# vvcc.net
KiCad netlist of a schematic drawn in EAGLE
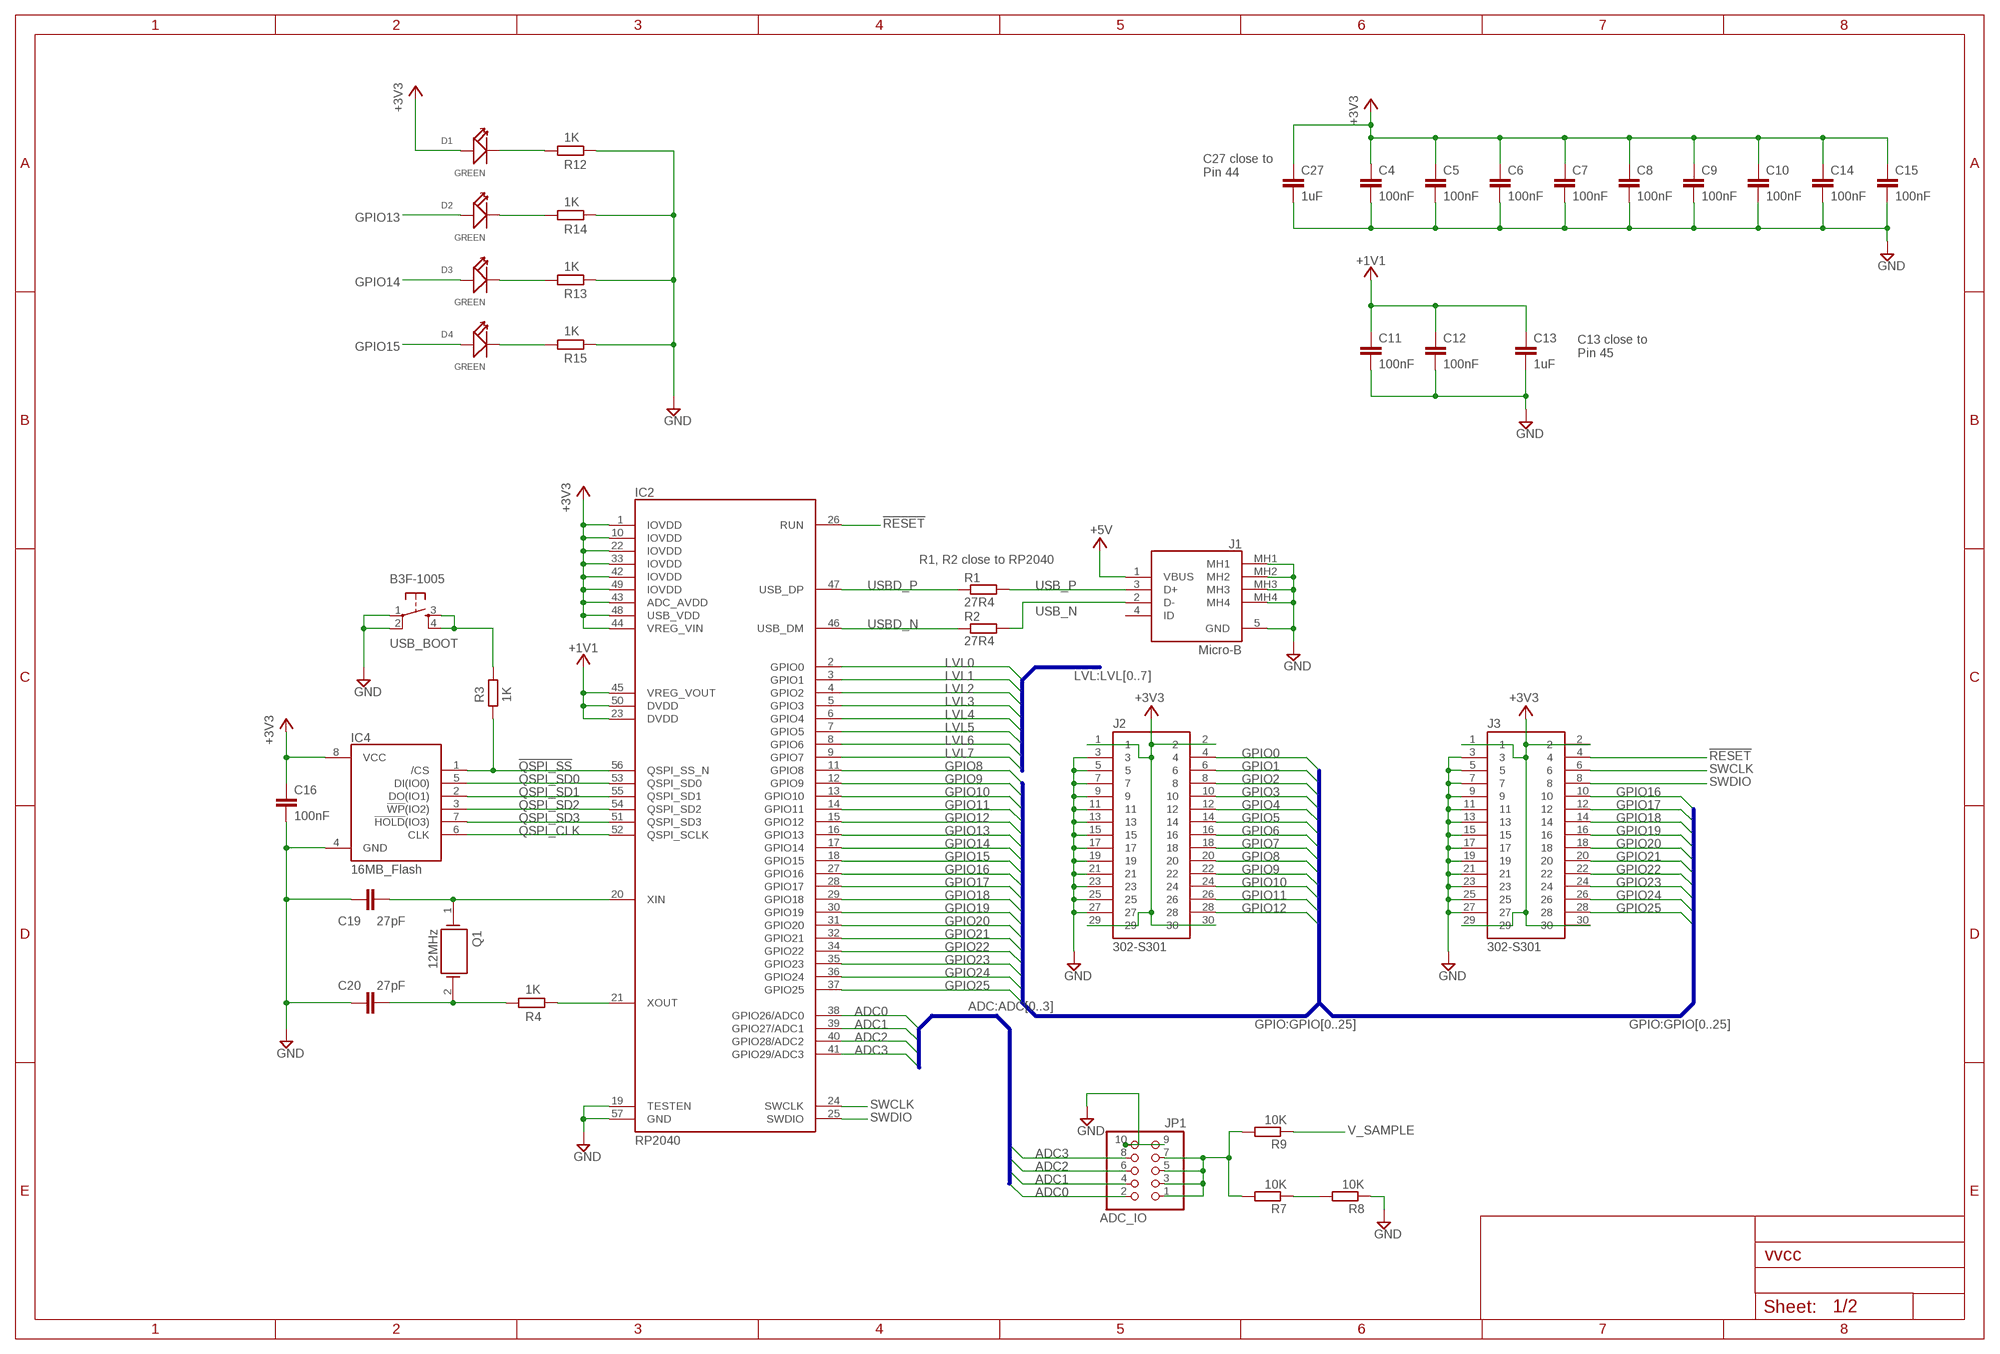
[diagram p0: schematic, sheet 1]
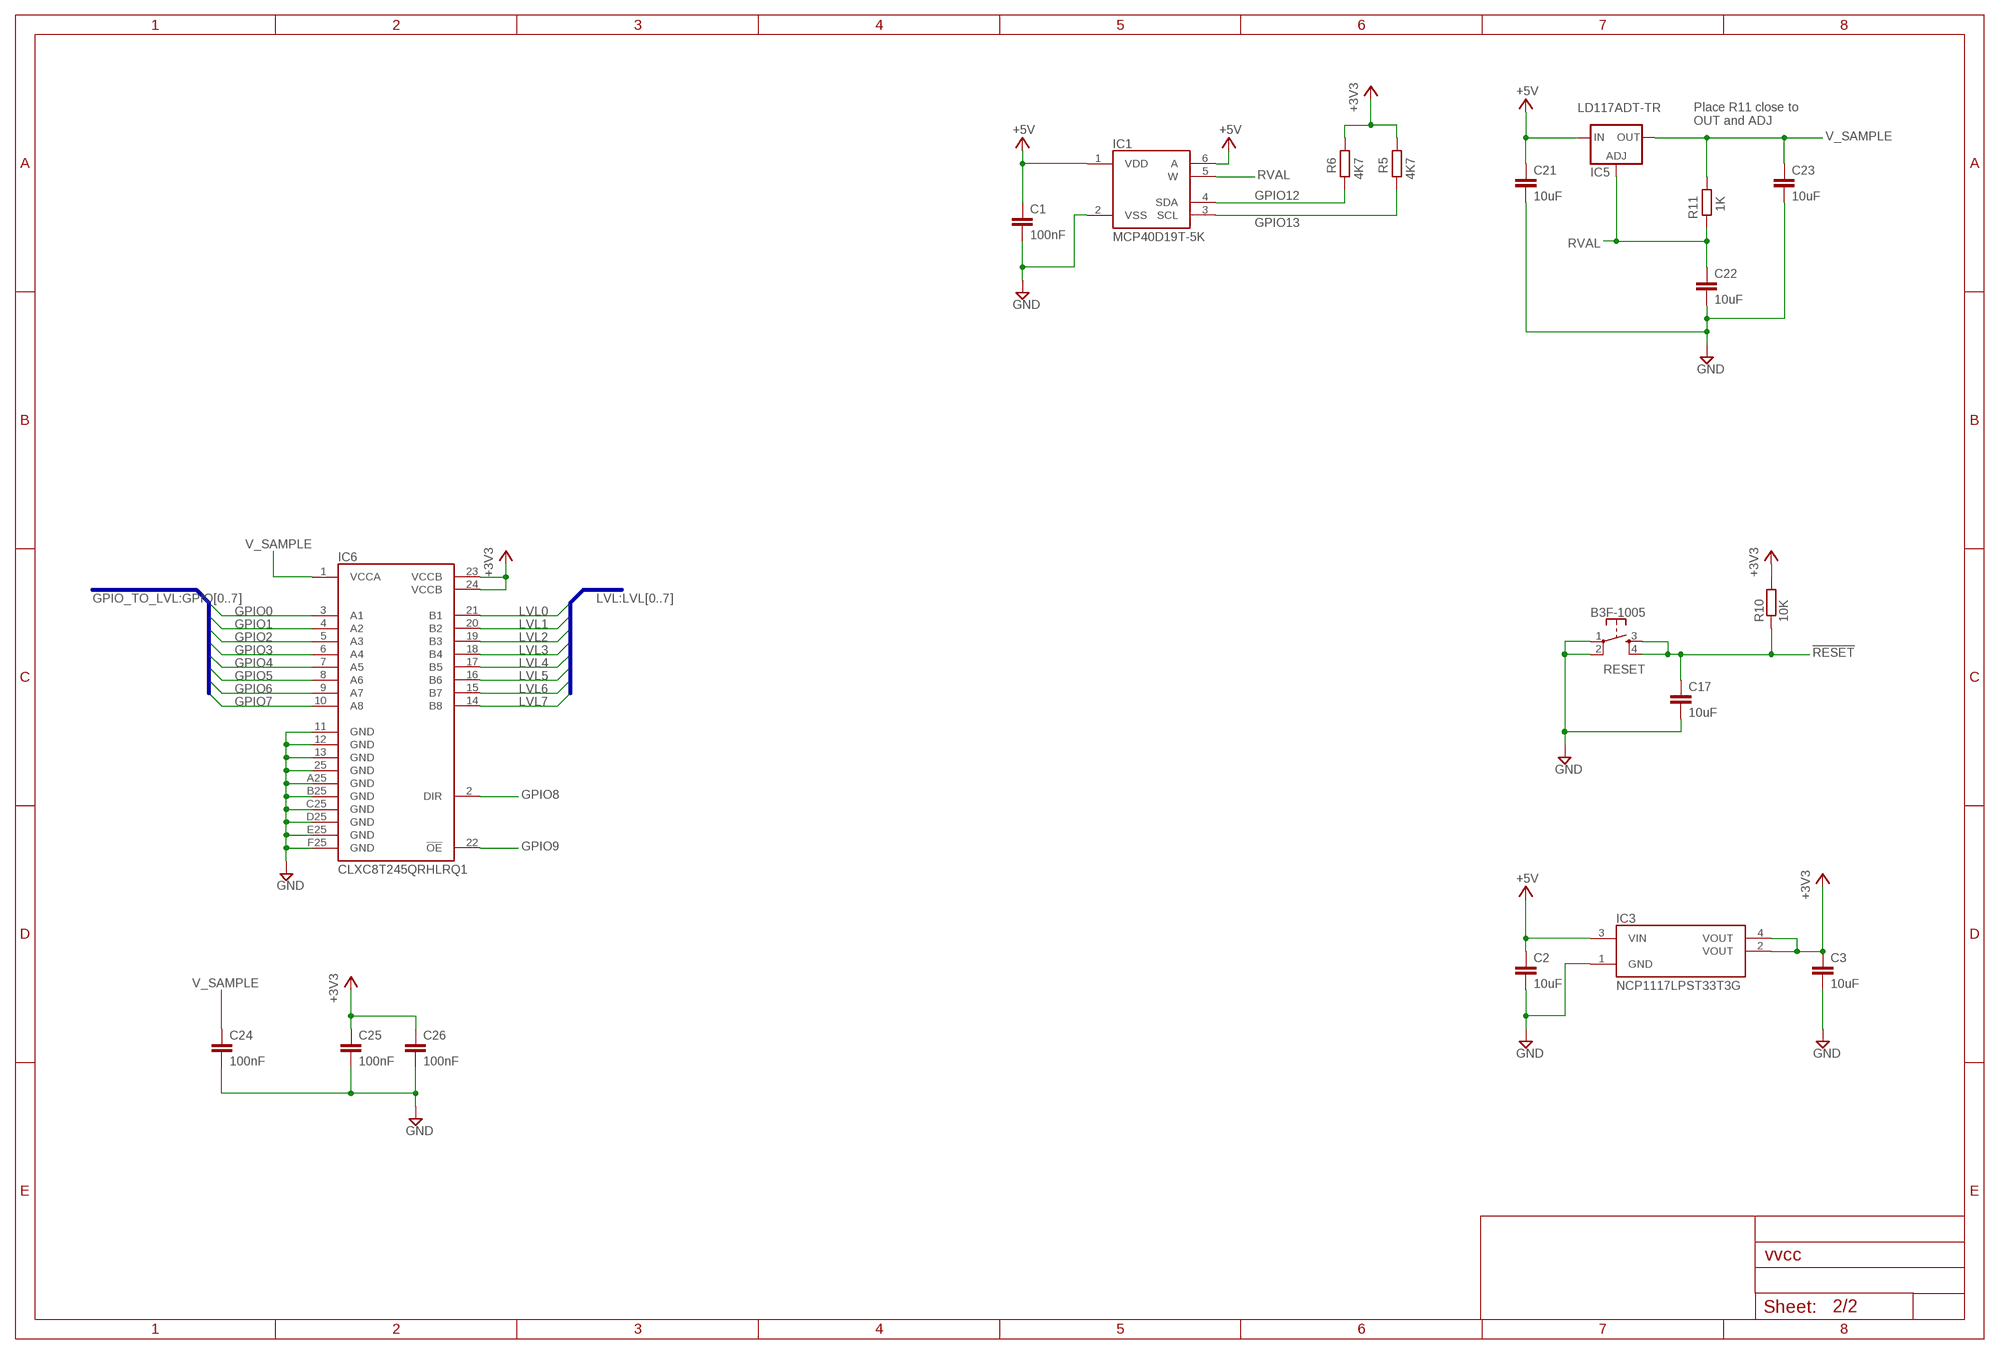
[diagram p1: schematic, sheet 2]

(export (version "E")
  (design (tool "Eeschema 10.0.6"))
  (components
    (comp (ref "C1")
      (value "100nF")
      (footprint "eagle-import:C0201")
      (libsource (lib "eagle-import") (part "C-EUC0201"))
    )
    (comp (ref "C2")
      (value "10uF")
      (footprint "eagle-import:C0402")
      (libsource (lib "eagle-import") (part "C-EUC0402"))
    )
    (comp (ref "C3")
      (value "10uF")
      (footprint "eagle-import:C0402")
      (libsource (lib "eagle-import") (part "C-EUC0402"))
    )
    (comp (ref "C17")
      (value "10uF")
      (footprint "eagle-import:C0402")
      (fields (field (name "USE") "GRM155R60J106ME15D"))
      (libsource (lib "eagle-import") (part "C-EUC0402"))
    )
    (comp (ref "C21")
      (value "10uF")
      (footprint "eagle-import:C0402")
      (libsource (lib "eagle-import") (part "C-EUC0402"))
    )
    (comp (ref "C22")
      (value "10uF")
      (footprint "eagle-import:C0402")
      (libsource (lib "eagle-import") (part "C-EUC0402"))
    )
    (comp (ref "C23")
      (value "10uF")
      (footprint "eagle-import:C0402")
      (libsource (lib "eagle-import") (part "C-EUC0402"))
    )
    (comp (ref "C24")
      (value "100nF")
      (footprint "eagle-import:C0201")
      (libsource (lib "eagle-import") (part "C-EUC0201"))
    )
    (comp (ref "C25")
      (value "100nF")
      (footprint "eagle-import:C0201")
      (libsource (lib "eagle-import") (part "C-EUC0201"))
    )
    (comp (ref "C26")
      (value "100nF")
      (footprint "eagle-import:C0201")
      (libsource (lib "eagle-import") (part "C-EUC0201"))
    )
    (comp (ref "IC1")
      (value "MCP40D19T-5K")
      (footprint "eagle-import:SOP65P210X110-6N")
      (fields
        (field (name "ARROW_PART_NUMBER") "MCP40D18T-104E/LT")
        (field (name "MOUSER_PART_NUMBER") "579-MCP40D18T104E/LT")
      )
      (libsource (lib "eagle-import") (part "MCP40D18T-104E_LT"))
    )
    (comp (ref "IC3")
      (value "NCP1117LPST33T3G")
      (footprint "eagle-import:SOT230P700X180-4N")
      (fields (field (name "MOUSER_PART_NUMBER") "863-NCP1117LPST33T3G"))
      (libsource (lib "eagle-import") (part "NCP1117LPST33T3G"))
    )
    (comp (ref "IC5")
      (value "LD117ADT-TR")
      (footprint "eagle-import:DPACK")
      (libsource (lib "eagle-import") (part "LD117A?DT-TR"))
    )
    (comp (ref "IC6")
      (value "CLXC8T245QRHLRQ1")
      (footprint "eagle-import:CLXC8T245QRHLRQ1")
      (fields (field (name "MOUSER_PART_NUMBER") "595-CLXC8T245QRHLRQ1"))
      (libsource (lib "eagle-import") (part "CLXC8T245QRHLRQ1"))
    )
    (comp (ref "R5")
      (value "4K7")
      (footprint "eagle-import:R0201")
      (libsource (lib "eagle-import") (part "R-EU_R0201"))
    )
    (comp (ref "R6")
      (value "4K7")
      (footprint "eagle-import:R0201")
      (libsource (lib "eagle-import") (part "R-EU_R0201"))
    )
    (comp (ref "R10")
      (value "10K")
      (footprint "eagle-import:R0201")
      (fields (field (name "USE") "CR0201-JW-103GLF"))
      (libsource (lib "eagle-import") (part "R-EU_R0201"))
    )
    (comp (ref "R11")
      (value "1K")
      (footprint "eagle-import:R0201")
      (libsource (lib "eagle-import") (part "R-EU_R0201"))
    )
    (comp (ref "RESET")
      (value "B3F-1005")
      (footprint "eagle-import:TACTILE-PTH")
      (fields (field (name "USE") "B3F-1005"))
      (libsource (lib "eagle-import") (part "TAC_SWITCHPTH"))
    )
    (comp (ref "C4")
      (value "100nF")
      (footprint "eagle-import:C0201")
      (libsource (lib "eagle-import") (part "C-EUC0201"))
    )
    (comp (ref "C5")
      (value "100nF")
      (footprint "eagle-import:C0201")
      (libsource (lib "eagle-import") (part "C-EUC0201"))
    )
    (comp (ref "C6")
      (value "100nF")
      (footprint "eagle-import:C0201")
      (libsource (lib "eagle-import") (part "C-EUC0201"))
    )
    (comp (ref "C7")
      (value "100nF")
      (footprint "eagle-import:C0201")
      (libsource (lib "eagle-import") (part "C-EUC0201"))
    )
    (comp (ref "C8")
      (value "100nF")
      (footprint "eagle-import:C0201")
      (libsource (lib "eagle-import") (part "C-EUC0201"))
    )
    (comp (ref "C9")
      (value "100nF")
      (footprint "eagle-import:C0201")
      (libsource (lib "eagle-import") (part "C-EUC0201"))
    )
    (comp (ref "C10")
      (value "100nF")
      (footprint "eagle-import:C0201")
      (libsource (lib "eagle-import") (part "C-EUC0201"))
    )
    (comp (ref "C11")
      (value "100nF")
      (footprint "eagle-import:C0201")
      (libsource (lib "eagle-import") (part "C-EUC0201"))
    )
    (comp (ref "C12")
      (value "100nF")
      (footprint "eagle-import:C0201")
      (libsource (lib "eagle-import") (part "C-EUC0201"))
    )
    (comp (ref "C13")
      (value "1uF")
      (footprint "eagle-import:C0201")
      (libsource (lib "eagle-import") (part "C-EUC0201"))
    )
    (comp (ref "C14")
      (value "100nF")
      (footprint "eagle-import:C0201")
      (libsource (lib "eagle-import") (part "C-EUC0201"))
    )
    (comp (ref "C15")
      (value "100nF")
      (footprint "eagle-import:C0201")
      (libsource (lib "eagle-import") (part "C-EUC0201"))
    )
    (comp (ref "C16")
      (value "100nF")
      (footprint "eagle-import:C0201")
      (libsource (lib "eagle-import") (part "C-EUC0201"))
    )
    (comp (ref "C19")
      (value "27pF")
      (footprint "eagle-import:C0201")
      (libsource (lib "eagle-import") (part "C-EUC0201"))
    )
    (comp (ref "C20")
      (value "27pF")
      (footprint "eagle-import:C0201")
      (libsource (lib "eagle-import") (part "C-EUC0201"))
    )
    (comp (ref "C27")
      (value "1uF")
      (footprint "eagle-import:C0201")
      (libsource (lib "eagle-import") (part "C-EUC0201"))
    )
    (comp (ref "D1")
      (value "GREEN")
      (footprint "eagle-import:LED-0603")
      (fields (field (name "MPN") "19-217-BHC-ZL1M2RY-3T"))
      (libsource (lib "eagle-import") (part "SMD-LED-CLEAR-BLUE(0603)"))
    )
    (comp (ref "D2")
      (value "GREEN")
      (footprint "eagle-import:LED-0603")
      (fields (field (name "MPN") "19-217-BHC-ZL1M2RY-3T"))
      (libsource (lib "eagle-import") (part "SMD-LED-CLEAR-BLUE(0603)"))
    )
    (comp (ref "D3")
      (value "GREEN")
      (footprint "eagle-import:LED-0603")
      (fields (field (name "MPN") "19-217-BHC-ZL1M2RY-3T"))
      (libsource (lib "eagle-import") (part "SMD-LED-CLEAR-BLUE(0603)"))
    )
    (comp (ref "D4")
      (value "GREEN")
      (footprint "eagle-import:LED-0603")
      (fields (field (name "MPN") "19-217-BHC-ZL1M2RY-3T"))
      (libsource (lib "eagle-import") (part "SMD-LED-CLEAR-BLUE(0603)"))
    )
    (comp (ref "IC2")
      (value "RP2040")
      (footprint "eagle-import:QFN40P700X700X90-57N")
      (libsource (lib "eagle-import") (part "RP2040"))
    )
    (comp (ref "IC4")
      (value "16MB_Flash")
      (footprint "eagle-import:SOIC127P790X216-8N")
      (fields
        (field (name "ARROW_PART_NUMBER") "W25Q128JVSIM TR")
        (field (name "MOUSER_PART_NUMBER") "454-W25Q128JVSIMTR")
      )
      (libsource (lib "eagle-import") (part "W25Q128JVSIM_TR"))
    )
    (comp (ref "J1")
      (value "Micro-B")
      (footprint "eagle-import:MCRBSRASMTCS14TR")
      (fields (field (name "ARROW_PART_NUMBER") "MCR-B-S-RA-SMT-CS14-T/R"))
      (libsource (lib "eagle-import") (part "MCR-B-S-RA-SMT-CS14-T_R"))
    )
    (comp (ref "J2")
      (value "302-S301")
      (footprint "eagle-import:SHDR30W66P254_2X15_4572X910X91")
      (libsource (lib "eagle-import") (part "302-S301"))
    )
    (comp (ref "J3")
      (value "302-S301")
      (footprint "eagle-import:SHDR30W66P254_2X15_4572X910X91")
      (libsource (lib "eagle-import") (part "302-S301"))
    )
    (comp (ref "JP1")
      (value "ADC_IO")
      (footprint "eagle-import:2X05")
      (libsource (lib "eagle-import") (part "PINHD-2X5"))
    )
    (comp (ref "Q1")
      (value "12MHz")
      (footprint "eagle-import:HC_49US-(AT49)_1")
      (fields
        (field (name "ARROW_PART_NUMBER") "ABLS-12.000MHZ-B4-T")
        (field (name "MOUSER_PART_NUMBER") "815-ABLS-12.0M-T")
      )
      (libsource (lib "eagle-import") (part "ABLS-12.000MHZ-B4-T"))
    )
    (comp (ref "R1")
      (value "27R4")
      (footprint "eagle-import:R0201")
      (libsource (lib "eagle-import") (part "R-EU_R0201"))
    )
    (comp (ref "R2")
      (value "27R4")
      (footprint "eagle-import:R0201")
      (libsource (lib "eagle-import") (part "R-EU_R0201"))
    )
    (comp (ref "R3")
      (value "1K")
      (footprint "eagle-import:R0201")
      (libsource (lib "eagle-import") (part "R-EU_R0201"))
    )
    (comp (ref "R4")
      (value "1K")
      (footprint "eagle-import:R0201")
      (libsource (lib "eagle-import") (part "R-EU_R0201"))
    )
    (comp (ref "R7")
      (value "10K")
      (footprint "eagle-import:R0201")
      (fields (field (name "USE") "CR0201-JW-103GLF"))
      (libsource (lib "eagle-import") (part "R-EU_R0201"))
    )
    (comp (ref "R8")
      (value "10K")
      (footprint "eagle-import:R0201")
      (fields (field (name "USE") "CR0201-JW-103GLF"))
      (libsource (lib "eagle-import") (part "R-EU_R0201"))
    )
    (comp (ref "R9")
      (value "10K")
      (footprint "eagle-import:R0201")
      (fields (field (name "USE") "CR0201-JW-103GLF"))
      (libsource (lib "eagle-import") (part "R-EU_R0201"))
    )
    (comp (ref "R12")
      (value "1K")
      (footprint "eagle-import:R0201")
      (libsource (lib "eagle-import") (part "R-EU_R0201"))
    )
    (comp (ref "R13")
      (value "1K")
      (footprint "eagle-import:R0201")
      (libsource (lib "eagle-import") (part "R-EU_R0201"))
    )
    (comp (ref "R14")
      (value "1K")
      (footprint "eagle-import:R0201")
      (libsource (lib "eagle-import") (part "R-EU_R0201"))
    )
    (comp (ref "R15")
      (value "1K")
      (footprint "eagle-import:R0201")
      (libsource (lib "eagle-import") (part "R-EU_R0201"))
    )
    (comp (ref "USB_BOOT")
      (value "B3F-1005")
      (footprint "eagle-import:TACTILE-PTH")
      (fields (field (name "USE") "B3F-1005"))
      (libsource (lib "eagle-import") (part "TAC_SWITCHPTH"))
    )
  )
  (nets
    (net (code "55") (name "+1.8_FT") (class "Default")
      (node (ref "C11") (pin "1") (pinfunction "1_1") (pintype "passive"))
      (node (ref "C12") (pin "1") (pinfunction "1_1") (pintype "passive"))
      (node (ref "C13") (pin "1") (pinfunction "1_1") (pintype "passive"))
      (node (ref "IC2") (pin "23") (pinfunction "DVDD_23") (pintype "bidirectional"))
      (node (ref "IC2") (pin "45") (pinfunction "VREG_VOUT_45") (pintype "bidirectional"))
      (node (ref "IC2") (pin "50") (pinfunction "DVDD_50") (pintype "bidirectional"))
    )
    (net (code "56") (name "+3V3") (class "Default")
      (node (ref "C10") (pin "1") (pinfunction "1_1") (pintype "passive"))
      (node (ref "C14") (pin "1") (pinfunction "1_1") (pintype "passive"))
      (node (ref "C15") (pin "1") (pinfunction "1_1") (pintype "passive"))
      (node (ref "C16") (pin "1") (pinfunction "1_1") (pintype "passive"))
      (node (ref "C25") (pin "1") (pinfunction "1_1") (pintype "passive"))
      (node (ref "C26") (pin "1") (pinfunction "1_1") (pintype "passive"))
      (node (ref "C27") (pin "1") (pinfunction "1_1") (pintype "passive"))
      (node (ref "C3") (pin "1") (pinfunction "1_1") (pintype "passive"))
      (node (ref "C4") (pin "1") (pinfunction "1_1") (pintype "passive"))
      (node (ref "C5") (pin "1") (pinfunction "1_1") (pintype "passive"))
      (node (ref "C6") (pin "1") (pinfunction "1_1") (pintype "passive"))
      (node (ref "C7") (pin "1") (pinfunction "1_1") (pintype "passive"))
      (node (ref "C8") (pin "1") (pinfunction "1_1") (pintype "passive"))
      (node (ref "C9") (pin "1") (pinfunction "1_1") (pintype "passive"))
      (node (ref "D1") (pin "+") (pinfunction "+_+") (pintype "passive"))
      (node (ref "IC2") (pin "1") (pinfunction "IOVDD_1") (pintype "bidirectional"))
      (node (ref "IC2") (pin "10") (pinfunction "IOVDD_10") (pintype "bidirectional"))
      (node (ref "IC2") (pin "22") (pinfunction "IOVDD_22") (pintype "bidirectional"))
      (node (ref "IC2") (pin "33") (pinfunction "IOVDD_33") (pintype "bidirectional"))
      (node (ref "IC2") (pin "42") (pinfunction "IOVDD_42") (pintype "bidirectional"))
      (node (ref "IC2") (pin "43") (pinfunction "ADC_AVDD_43") (pintype "bidirectional"))
      (node (ref "IC2") (pin "44") (pinfunction "VREG_VIN_44") (pintype "bidirectional"))
      (node (ref "IC2") (pin "48") (pinfunction "USB_VDD_48") (pintype "bidirectional"))
      (node (ref "IC2") (pin "49") (pinfunction "IOVDD_49") (pintype "bidirectional"))
      (node (ref "IC3") (pin "2") (pinfunction "VOUT_2") (pintype "bidirectional"))
      (node (ref "IC3") (pin "4") (pinfunction "VOUT_4") (pintype "bidirectional"))
      (node (ref "IC4") (pin "8") (pinfunction "VCC_8") (pintype "bidirectional"))
      (node (ref "IC6") (pin "23") (pinfunction "VCCB_23") (pintype "bidirectional"))
      (node (ref "IC6") (pin "24") (pinfunction "VCCB_24") (pintype "bidirectional"))
      (node (ref "J2") (pin "1") (pinfunction "1_1") (pintype "bidirectional"))
      (node (ref "J2") (pin "2") (pinfunction "2_2") (pintype "bidirectional"))
      (node (ref "J2") (pin "29") (pinfunction "29_29") (pintype "bidirectional"))
      (node (ref "J2") (pin "30") (pinfunction "30_30") (pintype "bidirectional"))
      (node (ref "J3") (pin "1") (pinfunction "1_1") (pintype "bidirectional"))
      (node (ref "J3") (pin "2") (pinfunction "2_2") (pintype "bidirectional"))
      (node (ref "J3") (pin "29") (pinfunction "29_29") (pintype "bidirectional"))
      (node (ref "J3") (pin "30") (pinfunction "30_30") (pintype "bidirectional"))
      (node (ref "R10") (pin "2") (pinfunction "2_2") (pintype "passive"))
      (node (ref "R5") (pin "1") (pinfunction "1_1") (pintype "passive"))
      (node (ref "R6") (pin "1") (pinfunction "1_1") (pintype "passive"))
    )
    (net (code "57") (name "+5V") (class "Default")
      (node (ref "C1") (pin "1") (pinfunction "1_1") (pintype "passive"))
      (node (ref "C2") (pin "1") (pinfunction "1_1") (pintype "passive"))
      (node (ref "C21") (pin "1") (pinfunction "1_1") (pintype "passive"))
      (node (ref "IC1") (pin "1") (pinfunction "VDD_1") (pintype "bidirectional"))
      (node (ref "IC1") (pin "6") (pinfunction "A_6") (pintype "bidirectional"))
      (node (ref "IC3") (pin "3") (pinfunction "VIN_3") (pintype "bidirectional"))
      (node (ref "IC5") (pin "3") (pinfunction "IN_3") (pintype "input"))
      (node (ref "J1") (pin "1") (pinfunction "VBUS_1") (pintype "bidirectional"))
    )
    (net (code "63") (name "ADC0") (class "Default")
      (node (ref "IC2") (pin "38") (pinfunction "GPIO26/ADC0_38") (pintype "bidirectional"))
      (node (ref "JP1") (pin "2") (pinfunction "2_2") (pintype "passive"))
    )
    (net (code "64") (name "ADC1") (class "Default")
      (node (ref "IC2") (pin "39") (pinfunction "GPIO27/ADC1_39") (pintype "bidirectional"))
      (node (ref "JP1") (pin "4") (pinfunction "4_4") (pintype "passive"))
    )
    (net (code "65") (name "ADC2") (class "Default")
      (node (ref "IC2") (pin "40") (pinfunction "GPIO28/ADC2_40") (pintype "bidirectional"))
      (node (ref "JP1") (pin "6") (pinfunction "6_6") (pintype "passive"))
    )
    (net (code "66") (name "ADC3") (class "Default")
      (node (ref "IC2") (pin "41") (pinfunction "GPIO29/ADC3_41") (pintype "bidirectional"))
      (node (ref "JP1") (pin "8") (pinfunction "8_8") (pintype "passive"))
    )
    (net (code "67") (name "GND") (class "Default")
      (node (ref "C1") (pin "2") (pinfunction "2_2") (pintype "passive"))
      (node (ref "C10") (pin "2") (pinfunction "2_2") (pintype "passive"))
      (node (ref "C11") (pin "2") (pinfunction "2_2") (pintype "passive"))
      (node (ref "C12") (pin "2") (pinfunction "2_2") (pintype "passive"))
      (node (ref "C13") (pin "2") (pinfunction "2_2") (pintype "passive"))
      (node (ref "C14") (pin "2") (pinfunction "2_2") (pintype "passive"))
      (node (ref "C15") (pin "2") (pinfunction "2_2") (pintype "passive"))
      (node (ref "C16") (pin "2") (pinfunction "2_2") (pintype "passive"))
      (node (ref "C17") (pin "2") (pinfunction "2_2") (pintype "passive"))
      (node (ref "C19") (pin "2") (pinfunction "2_2") (pintype "passive"))
      (node (ref "C2") (pin "2") (pinfunction "2_2") (pintype "passive"))
      (node (ref "C20") (pin "1") (pinfunction "1_1") (pintype "passive"))
      (node (ref "C21") (pin "2") (pinfunction "2_2") (pintype "passive"))
      (node (ref "C22") (pin "2") (pinfunction "2_2") (pintype "passive"))
      (node (ref "C23") (pin "2") (pinfunction "2_2") (pintype "passive"))
      (node (ref "C24") (pin "2") (pinfunction "2_2") (pintype "passive"))
      (node (ref "C25") (pin "2") (pinfunction "2_2") (pintype "passive"))
      (node (ref "C26") (pin "2") (pinfunction "2_2") (pintype "passive"))
      (node (ref "C27") (pin "2") (pinfunction "2_2") (pintype "passive"))
      (node (ref "C3") (pin "2") (pinfunction "2_2") (pintype "passive"))
      (node (ref "C4") (pin "2") (pinfunction "2_2") (pintype "passive"))
      (node (ref "C5") (pin "2") (pinfunction "2_2") (pintype "passive"))
      (node (ref "C6") (pin "2") (pinfunction "2_2") (pintype "passive"))
      (node (ref "C7") (pin "2") (pinfunction "2_2") (pintype "passive"))
      (node (ref "C8") (pin "2") (pinfunction "2_2") (pintype "passive"))
      (node (ref "C9") (pin "2") (pinfunction "2_2") (pintype "passive"))
      (node (ref "IC1") (pin "2") (pinfunction "VSS_2") (pintype "bidirectional"))
      (node (ref "IC2") (pin "19") (pinfunction "TESTEN_19") (pintype "bidirectional"))
      (node (ref "IC2") (pin "57") (pinfunction "GND_57") (pintype "bidirectional"))
      (node (ref "IC3") (pin "1") (pinfunction "GND_1") (pintype "bidirectional"))
      (node (ref "IC4") (pin "4") (pinfunction "GND_4") (pintype "bidirectional"))
      (node (ref "IC6") (pin "11") (pinfunction "GND_11") (pintype "bidirectional"))
      (node (ref "IC6") (pin "12") (pinfunction "GND_12") (pintype "bidirectional"))
      (node (ref "IC6") (pin "13") (pinfunction "GND_13") (pintype "bidirectional"))
      (node (ref "IC6") (pin "25") (pinfunction "GND_25") (pintype "bidirectional"))
      (node (ref "IC6") (pin "A25") (pinfunction "GND_A25") (pintype "bidirectional"))
      (node (ref "IC6") (pin "B25") (pinfunction "GND_B25") (pintype "bidirectional"))
      (node (ref "IC6") (pin "C25") (pinfunction "GND_C25") (pintype "bidirectional"))
      (node (ref "IC6") (pin "D25") (pinfunction "GND_D25") (pintype "bidirectional"))
      (node (ref "IC6") (pin "E25") (pinfunction "GND_E25") (pintype "bidirectional"))
      (node (ref "IC6") (pin "F25") (pinfunction "GND_F25") (pintype "bidirectional"))
      (node (ref "J1") (pin "5") (pinfunction "GND_5") (pintype "bidirectional"))
      (node (ref "J1") (pin "MH1") (pinfunction "MH1_MH1") (pintype "bidirectional"))
      (node (ref "J1") (pin "MH2") (pinfunction "MH2_MH2") (pintype "bidirectional"))
      (node (ref "J1") (pin "MH3") (pinfunction "MH3_MH3") (pintype "bidirectional"))
      (node (ref "J1") (pin "MH4") (pinfunction "MH4_MH4") (pintype "bidirectional"))
      (node (ref "J2") (pin "11") (pinfunction "11_11") (pintype "bidirectional"))
      (node (ref "J2") (pin "13") (pinfunction "13_13") (pintype "bidirectional"))
      (node (ref "J2") (pin "15") (pinfunction "15_15") (pintype "bidirectional"))
      (node (ref "J2") (pin "17") (pinfunction "17_17") (pintype "bidirectional"))
      (node (ref "J2") (pin "19") (pinfunction "19_19") (pintype "bidirectional"))
      (node (ref "J2") (pin "21") (pinfunction "21_21") (pintype "bidirectional"))
      (node (ref "J2") (pin "23") (pinfunction "23_23") (pintype "bidirectional"))
      (node (ref "J2") (pin "25") (pinfunction "25_25") (pintype "bidirectional"))
      (node (ref "J2") (pin "27") (pinfunction "27_27") (pintype "bidirectional"))
      (node (ref "J2") (pin "3") (pinfunction "3_3") (pintype "bidirectional"))
      (node (ref "J2") (pin "5") (pinfunction "5_5") (pintype "bidirectional"))
      (node (ref "J2") (pin "7") (pinfunction "7_7") (pintype "bidirectional"))
      (node (ref "J2") (pin "9") (pinfunction "9_9") (pintype "bidirectional"))
      (node (ref "J3") (pin "11") (pinfunction "11_11") (pintype "bidirectional"))
      (node (ref "J3") (pin "13") (pinfunction "13_13") (pintype "bidirectional"))
      (node (ref "J3") (pin "15") (pinfunction "15_15") (pintype "bidirectional"))
      (node (ref "J3") (pin "17") (pinfunction "17_17") (pintype "bidirectional"))
      (node (ref "J3") (pin "19") (pinfunction "19_19") (pintype "bidirectional"))
      (node (ref "J3") (pin "21") (pinfunction "21_21") (pintype "bidirectional"))
      (node (ref "J3") (pin "23") (pinfunction "23_23") (pintype "bidirectional"))
      (node (ref "J3") (pin "25") (pinfunction "25_25") (pintype "bidirectional"))
      (node (ref "J3") (pin "27") (pinfunction "27_27") (pintype "bidirectional"))
      (node (ref "J3") (pin "3") (pinfunction "3_3") (pintype "bidirectional"))
      (node (ref "J3") (pin "5") (pinfunction "5_5") (pintype "bidirectional"))
      (node (ref "J3") (pin "7") (pinfunction "7_7") (pintype "bidirectional"))
      (node (ref "J3") (pin "9") (pinfunction "9_9") (pintype "bidirectional"))
      (node (ref "JP1") (pin "10") (pinfunction "10_10") (pintype "passive"))
      (node (ref "JP1") (pin "9") (pinfunction "9_9") (pintype "passive"))
      (node (ref "R12") (pin "2") (pinfunction "2_2") (pintype "passive"))
      (node (ref "R13") (pin "2") (pinfunction "2_2") (pintype "passive"))
      (node (ref "R14") (pin "2") (pinfunction "2_2") (pintype "passive"))
      (node (ref "R15") (pin "2") (pinfunction "2_2") (pintype "passive"))
      (node (ref "R8") (pin "1") (pinfunction "1_1") (pintype "passive"))
      (node (ref "RESET") (pin "1") (pinfunction "1_1") (pintype "passive"))
      (node (ref "RESET") (pin "2") (pinfunction "2_2") (pintype "passive"))
      (node (ref "USB_BOOT") (pin "1") (pinfunction "1_1") (pintype "passive"))
      (node (ref "USB_BOOT") (pin "2") (pinfunction "2_2") (pintype "passive"))
    )
    (net (code "68") (name "GPIO0") (class "Default")
      (node (ref "IC6") (pin "3") (pinfunction "A1_3") (pintype "bidirectional"))
      (node (ref "J2") (pin "4") (pinfunction "4_4") (pintype "bidirectional"))
    )
    (net (code "69") (name "GPIO1") (class "Default")
      (node (ref "IC6") (pin "4") (pinfunction "A2_4") (pintype "bidirectional"))
      (node (ref "J2") (pin "6") (pinfunction "6_6") (pintype "bidirectional"))
    )
    (net (code "70") (name "GPIO2") (class "Default")
      (node (ref "IC6") (pin "5") (pinfunction "A3_5") (pintype "bidirectional"))
      (node (ref "J2") (pin "8") (pinfunction "8_8") (pintype "bidirectional"))
    )
    (net (code "71") (name "GPIO3") (class "Default")
      (node (ref "IC6") (pin "6") (pinfunction "A4_6") (pintype "bidirectional"))
      (node (ref "J2") (pin "10") (pinfunction "10_10") (pintype "bidirectional"))
    )
    (net (code "72") (name "GPIO4") (class "Default")
      (node (ref "IC6") (pin "7") (pinfunction "A5_7") (pintype "bidirectional"))
      (node (ref "J2") (pin "12") (pinfunction "12_12") (pintype "bidirectional"))
    )
    (net (code "73") (name "GPIO5") (class "Default")
      (node (ref "IC6") (pin "8") (pinfunction "A6_8") (pintype "bidirectional"))
      (node (ref "J2") (pin "14") (pinfunction "14_14") (pintype "bidirectional"))
    )
    (net (code "74") (name "GPIO6") (class "Default")
      (node (ref "IC6") (pin "9") (pinfunction "A7_9") (pintype "bidirectional"))
      (node (ref "J2") (pin "16") (pinfunction "16_16") (pintype "bidirectional"))
    )
    (net (code "75") (name "GPIO7") (class "Default")
      (node (ref "IC6") (pin "10") (pinfunction "A8_10") (pintype "bidirectional"))
      (node (ref "J2") (pin "18") (pinfunction "18_18") (pintype "bidirectional"))
    )
    (net (code "76") (name "GPIO8") (class "Default")
      (node (ref "IC2") (pin "11") (pinfunction "GPIO8_11") (pintype "bidirectional"))
      (node (ref "IC6") (pin "2") (pinfunction "DIR_2") (pintype "bidirectional"))
      (node (ref "J2") (pin "20") (pinfunction "20_20") (pintype "bidirectional"))
    )
    (net (code "77") (name "GPIO9") (class "Default")
      (node (ref "IC2") (pin "12") (pinfunction "GPIO9_12") (pintype "bidirectional"))
      (node (ref "IC6") (pin "22") (pinfunction "~{OE}_22") (pintype "bidirectional"))
      (node (ref "J2") (pin "22") (pinfunction "22_22") (pintype "bidirectional"))
    )
    (net (code "78") (name "GPIO10") (class "Default")
      (node (ref "IC2") (pin "13") (pinfunction "GPIO10_13") (pintype "bidirectional"))
      (node (ref "J2") (pin "24") (pinfunction "24_24") (pintype "bidirectional"))
    )
    (net (code "79") (name "GPIO11") (class "Default")
      (node (ref "IC2") (pin "14") (pinfunction "GPIO11_14") (pintype "bidirectional"))
      (node (ref "J2") (pin "26") (pinfunction "26_26") (pintype "bidirectional"))
    )
    (net (code "80") (name "GPIO12") (class "Default")
      (node (ref "IC1") (pin "4") (pinfunction "SDA_4") (pintype "bidirectional"))
      (node (ref "IC2") (pin "15") (pinfunction "GPIO12_15") (pintype "bidirectional"))
      (node (ref "J2") (pin "28") (pinfunction "28_28") (pintype "bidirectional"))
      (node (ref "R6") (pin "2") (pinfunction "2_2") (pintype "passive"))
    )
    (net (code "81") (name "GPIO13") (class "Default")
      (node (ref "D2") (pin "+") (pinfunction "+_+") (pintype "passive"))
      (node (ref "IC1") (pin "3") (pinfunction "SCL_3") (pintype "bidirectional"))
      (node (ref "IC2") (pin "16") (pinfunction "GPIO13_16") (pintype "bidirectional"))
      (node (ref "R5") (pin "2") (pinfunction "2_2") (pintype "passive"))
    )
    (net (code "82") (name "GPIO14") (class "Default")
      (node (ref "D3") (pin "+") (pinfunction "+_+") (pintype "passive"))
      (node (ref "IC2") (pin "17") (pinfunction "GPIO14_17") (pintype "bidirectional"))
    )
    (net (code "83") (name "GPIO15") (class "Default")
      (node (ref "D4") (pin "+") (pinfunction "+_+") (pintype "passive"))
      (node (ref "IC2") (pin "18") (pinfunction "GPIO15_18") (pintype "bidirectional"))
    )
    (net (code "84") (name "GPIO16") (class "Default")
      (node (ref "IC2") (pin "27") (pinfunction "GPIO16_27") (pintype "bidirectional"))
      (node (ref "J3") (pin "10") (pinfunction "10_10") (pintype "bidirectional"))
    )
    (net (code "85") (name "GPIO17") (class "Default")
      (node (ref "IC2") (pin "28") (pinfunction "GPIO17_28") (pintype "bidirectional"))
      (node (ref "J3") (pin "12") (pinfunction "12_12") (pintype "bidirectional"))
    )
    (net (code "86") (name "GPIO18") (class "Default")
      (node (ref "IC2") (pin "29") (pinfunction "GPIO18_29") (pintype "bidirectional"))
      (node (ref "J3") (pin "14") (pinfunction "14_14") (pintype "bidirectional"))
    )
    (net (code "87") (name "GPIO19") (class "Default")
      (node (ref "IC2") (pin "30") (pinfunction "GPIO19_30") (pintype "bidirectional"))
      (node (ref "J3") (pin "16") (pinfunction "16_16") (pintype "bidirectional"))
    )
    (net (code "88") (name "GPIO20") (class "Default")
      (node (ref "IC2") (pin "31") (pinfunction "GPIO20_31") (pintype "bidirectional"))
      (node (ref "J3") (pin "18") (pinfunction "18_18") (pintype "bidirectional"))
    )
    (net (code "89") (name "GPIO21") (class "Default")
      (node (ref "IC2") (pin "32") (pinfunction "GPIO21_32") (pintype "bidirectional"))
      (node (ref "J3") (pin "20") (pinfunction "20_20") (pintype "bidirectional"))
    )
    (net (code "90") (name "GPIO22") (class "Default")
      (node (ref "IC2") (pin "34") (pinfunction "GPIO22_34") (pintype "bidirectional"))
      (node (ref "J3") (pin "22") (pinfunction "22_22") (pintype "bidirectional"))
    )
    (net (code "91") (name "GPIO23") (class "Default")
      (node (ref "IC2") (pin "35") (pinfunction "GPIO23_35") (pintype "bidirectional"))
      (node (ref "J3") (pin "24") (pinfunction "24_24") (pintype "bidirectional"))
    )
    (net (code "92") (name "GPIO24") (class "Default")
      (node (ref "IC2") (pin "36") (pinfunction "GPIO24_36") (pintype "bidirectional"))
      (node (ref "J3") (pin "26") (pinfunction "26_26") (pintype "bidirectional"))
    )
    (net (code "93") (name "GPIO25") (class "Default")
      (node (ref "IC2") (pin "37") (pinfunction "GPIO25_37") (pintype "bidirectional"))
      (node (ref "J3") (pin "28") (pinfunction "28_28") (pintype "bidirectional"))
    )
    (net (code "94") (name "LVL0") (class "Default")
      (node (ref "IC2") (pin "2") (pinfunction "GPIO0_2") (pintype "bidirectional"))
      (node (ref "IC6") (pin "21") (pinfunction "B1_21") (pintype "bidirectional"))
    )
    (net (code "95") (name "LVL1") (class "Default")
      (node (ref "IC2") (pin "3") (pinfunction "GPIO1_3") (pintype "bidirectional"))
      (node (ref "IC6") (pin "20") (pinfunction "B2_20") (pintype "bidirectional"))
    )
    (net (code "96") (name "LVL2") (class "Default")
      (node (ref "IC2") (pin "4") (pinfunction "GPIO2_4") (pintype "bidirectional"))
      (node (ref "IC6") (pin "19") (pinfunction "B3_19") (pintype "bidirectional"))
    )
    (net (code "97") (name "LVL3") (class "Default")
      (node (ref "IC2") (pin "5") (pinfunction "GPIO3_5") (pintype "bidirectional"))
      (node (ref "IC6") (pin "18") (pinfunction "B4_18") (pintype "bidirectional"))
    )
    (net (code "98") (name "LVL4") (class "Default")
      (node (ref "IC2") (pin "6") (pinfunction "GPIO4_6") (pintype "bidirectional"))
      (node (ref "IC6") (pin "17") (pinfunction "B5_17") (pintype "bidirectional"))
    )
    (net (code "99") (name "LVL5") (class "Default")
      (node (ref "IC2") (pin "7") (pinfunction "GPIO5_7") (pintype "bidirectional"))
      (node (ref "IC6") (pin "16") (pinfunction "B6_16") (pintype "bidirectional"))
    )
    (net (code "100") (name "LVL6") (class "Default")
      (node (ref "IC2") (pin "8") (pinfunction "GPIO6_8") (pintype "bidirectional"))
      (node (ref "IC6") (pin "15") (pinfunction "B7_15") (pintype "bidirectional"))
    )
    (net (code "101") (name "LVL7") (class "Default")
      (node (ref "IC2") (pin "9") (pinfunction "GPIO7_9") (pintype "bidirectional"))
      (node (ref "IC6") (pin "14") (pinfunction "B8_14") (pintype "bidirectional"))
    )
    (net (code "102") (name "Net-(C20-Pad2)") (class "Default")
      (node (ref "C20") (pin "2") (pinfunction "2_2") (pintype "passive"))
      (node (ref "Q1") (pin "2") (pinfunction "2_2") (pintype "bidirectional"))
      (node (ref "R4") (pin "1") (pinfunction "1_1") (pintype "passive"))
    )
    (net (code "103") (name "Net-(D1-Pad-)") (class "Default")
      (node (ref "D1") (pin "-") (pinfunction "-_-") (pintype "passive"))
      (node (ref "R12") (pin "1") (pinfunction "1_1") (pintype "passive"))
    )
    (net (code "104") (name "Net-(D2-Pad-)") (class "Default")
      (node (ref "D2") (pin "-") (pinfunction "-_-") (pintype "passive"))
      (node (ref "R14") (pin "1") (pinfunction "1_1") (pintype "passive"))
    )
    (net (code "105") (name "Net-(D3-Pad-)") (class "Default")
      (node (ref "D3") (pin "-") (pinfunction "-_-") (pintype "passive"))
      (node (ref "R13") (pin "1") (pinfunction "1_1") (pintype "passive"))
    )
    (net (code "106") (name "Net-(D4-Pad-)") (class "Default")
      (node (ref "D4") (pin "-") (pinfunction "-_-") (pintype "passive"))
      (node (ref "R15") (pin "1") (pinfunction "1_1") (pintype "passive"))
    )
    (net (code "107") (name "Net-(IC2-XIN)") (class "Default")
      (node (ref "C19") (pin "1") (pinfunction "1_1") (pintype "passive"))
      (node (ref "IC2") (pin "20") (pinfunction "XIN_20") (pintype "bidirectional"))
      (node (ref "Q1") (pin "1") (pinfunction "1_1") (pintype "bidirectional"))
    )
    (net (code "108") (name "Net-(IC2-XOUT)") (class "Default")
      (node (ref "IC2") (pin "21") (pinfunction "XOUT_21") (pintype "bidirectional"))
      (node (ref "R4") (pin "2") (pinfunction "2_2") (pintype "passive"))
    )
    (net (code "109") (name "Net-(JP1-Pad1)") (class "Default")
      (node (ref "JP1") (pin "1") (pinfunction "1_1") (pintype "passive"))
      (node (ref "JP1") (pin "3") (pinfunction "3_3") (pintype "passive"))
      (node (ref "JP1") (pin "5") (pinfunction "5_5") (pintype "passive"))
      (node (ref "JP1") (pin "7") (pinfunction "7_7") (pintype "passive"))
      (node (ref "R7") (pin "2") (pinfunction "2_2") (pintype "passive"))
      (node (ref "R9") (pin "2") (pinfunction "2_2") (pintype "passive"))
    )
    (net (code "110") (name "Net-(R3-Pad1)") (class "Default")
      (node (ref "R3") (pin "1") (pinfunction "1_1") (pintype "passive"))
      (node (ref "USB_BOOT") (pin "3") (pinfunction "3_3") (pintype "passive"))
      (node (ref "USB_BOOT") (pin "4") (pinfunction "4_4") (pintype "passive"))
    )
    (net (code "111") (name "Net-(R7-Pad1)") (class "Default")
      (node (ref "R7") (pin "1") (pinfunction "1_1") (pintype "passive"))
      (node (ref "R8") (pin "2") (pinfunction "2_2") (pintype "passive"))
    )
    (net (code "112") (name "QSPI_CLK") (class "Default")
      (node (ref "IC2") (pin "52") (pinfunction "QSPI_SCLK_52") (pintype "bidirectional"))
      (node (ref "IC4") (pin "6") (pinfunction "CLK_6") (pintype "bidirectional"))
    )
    (net (code "113") (name "QSPI_SD0") (class "Default")
      (node (ref "IC2") (pin "53") (pinfunction "QSPI_SD0_53") (pintype "bidirectional"))
      (node (ref "IC4") (pin "5") (pinfunction "DI(IO0)_5") (pintype "bidirectional"))
    )
    (net (code "114") (name "QSPI_SD1") (class "Default")
      (node (ref "IC2") (pin "55") (pinfunction "QSPI_SD1_55") (pintype "bidirectional"))
      (node (ref "IC4") (pin "2") (pinfunction "DO(IO1)_2") (pintype "bidirectional"))
    )
    (net (code "115") (name "QSPI_SD2") (class "Default")
      (node (ref "IC2") (pin "54") (pinfunction "QSPI_SD2_54") (pintype "bidirectional"))
      (node (ref "IC4") (pin "3") (pinfunction "~{WP}(IO2)_3") (pintype "bidirectional"))
    )
    (net (code "116") (name "QSPI_SD3") (class "Default")
      (node (ref "IC2") (pin "51") (pinfunction "QSPI_SD3_51") (pintype "bidirectional"))
      (node (ref "IC4") (pin "7") (pinfunction "~{HOLD}(IO3)_7") (pintype "bidirectional"))
    )
    (net (code "117") (name "RVAL") (class "Default")
      (node (ref "C22") (pin "1") (pinfunction "1_1") (pintype "passive"))
      (node (ref "IC1") (pin "5") (pinfunction "W_5") (pintype "bidirectional"))
      (node (ref "IC5") (pin "1") (pinfunction "ADJ_1") (pintype "input"))
      (node (ref "R11") (pin "2") (pinfunction "2_2") (pintype "passive"))
    )
    (net (code "118") (name "SWCLK") (class "Default")
      (node (ref "IC2") (pin "24") (pinfunction "SWCLK_24") (pintype "bidirectional"))
      (node (ref "J3") (pin "6") (pinfunction "6_6") (pintype "bidirectional"))
    )
    (net (code "119") (name "SWDIO") (class "Default")
      (node (ref "IC2") (pin "25") (pinfunction "SWDIO_25") (pintype "bidirectional"))
      (node (ref "J3") (pin "8") (pinfunction "8_8") (pintype "bidirectional"))
    )
    (net (code "120") (name "USBD_N") (class "Default")
      (node (ref "IC2") (pin "46") (pinfunction "USB_DM_46") (pintype "bidirectional"))
      (node (ref "R2") (pin "1") (pinfunction "1_1") (pintype "passive"))
    )
    (net (code "121") (name "USBD_P") (class "Default")
      (node (ref "IC2") (pin "47") (pinfunction "USB_DP_47") (pintype "bidirectional"))
      (node (ref "R1") (pin "1") (pinfunction "1_1") (pintype "passive"))
    )
    (net (code "122") (name "USB_N") (class "Default")
      (node (ref "J1") (pin "2") (pinfunction "D-_2") (pintype "bidirectional"))
      (node (ref "R2") (pin "2") (pinfunction "2_2") (pintype "passive"))
    )
    (net (code "123") (name "USB_P") (class "Default")
      (node (ref "J1") (pin "3") (pinfunction "D+_3") (pintype "bidirectional"))
      (node (ref "R1") (pin "2") (pinfunction "2_2") (pintype "passive"))
    )
    (net (code "124") (name "V_SAMPLE") (class "Default")
      (node (ref "C23") (pin "1") (pinfunction "1_1") (pintype "passive"))
      (node (ref "C24") (pin "1") (pinfunction "1_1") (pintype "passive"))
      (node (ref "IC5") (pin "4") (pinfunction "OUT_4") (pintype "passive"))
      (node (ref "IC6") (pin "1") (pinfunction "VCCA_1") (pintype "bidirectional"))
      (node (ref "R11") (pin "1") (pinfunction "1_1") (pintype "passive"))
      (node (ref "R9") (pin "1") (pinfunction "1_1") (pintype "passive"))
    )
    (net (code "125") (name "unconnected-(J1-ID-Pad4)") (class "Default")
      (node (ref "J1") (pin "4") (pinfunction "ID_4") (pintype "bidirectional"))
    )
    (net (code "126") (name "~{QSPI_SS}") (class "Default")
      (node (ref "IC2") (pin "56") (pinfunction "QSPI_SS_N_56") (pintype "bidirectional"))
      (node (ref "IC4") (pin "1") (pinfunction "/CS_1") (pintype "bidirectional"))
      (node (ref "R3") (pin "2") (pinfunction "2_2") (pintype "passive"))
    )
    (net (code "127") (name "~{RESET}") (class "Default")
      (node (ref "C17") (pin "1") (pinfunction "1_1") (pintype "passive"))
      (node (ref "IC2") (pin "26") (pinfunction "RUN_26") (pintype "bidirectional"))
      (node (ref "J3") (pin "4") (pinfunction "4_4") (pintype "bidirectional"))
      (node (ref "R10") (pin "1") (pinfunction "1_1") (pintype "passive"))
      (node (ref "RESET") (pin "3") (pinfunction "3_3") (pintype "passive"))
      (node (ref "RESET") (pin "4") (pinfunction "4_4") (pintype "passive"))
    )
  )
)
